# Block_Diagram.net
KiCad netlist of a schematic drawn in Altium Designer
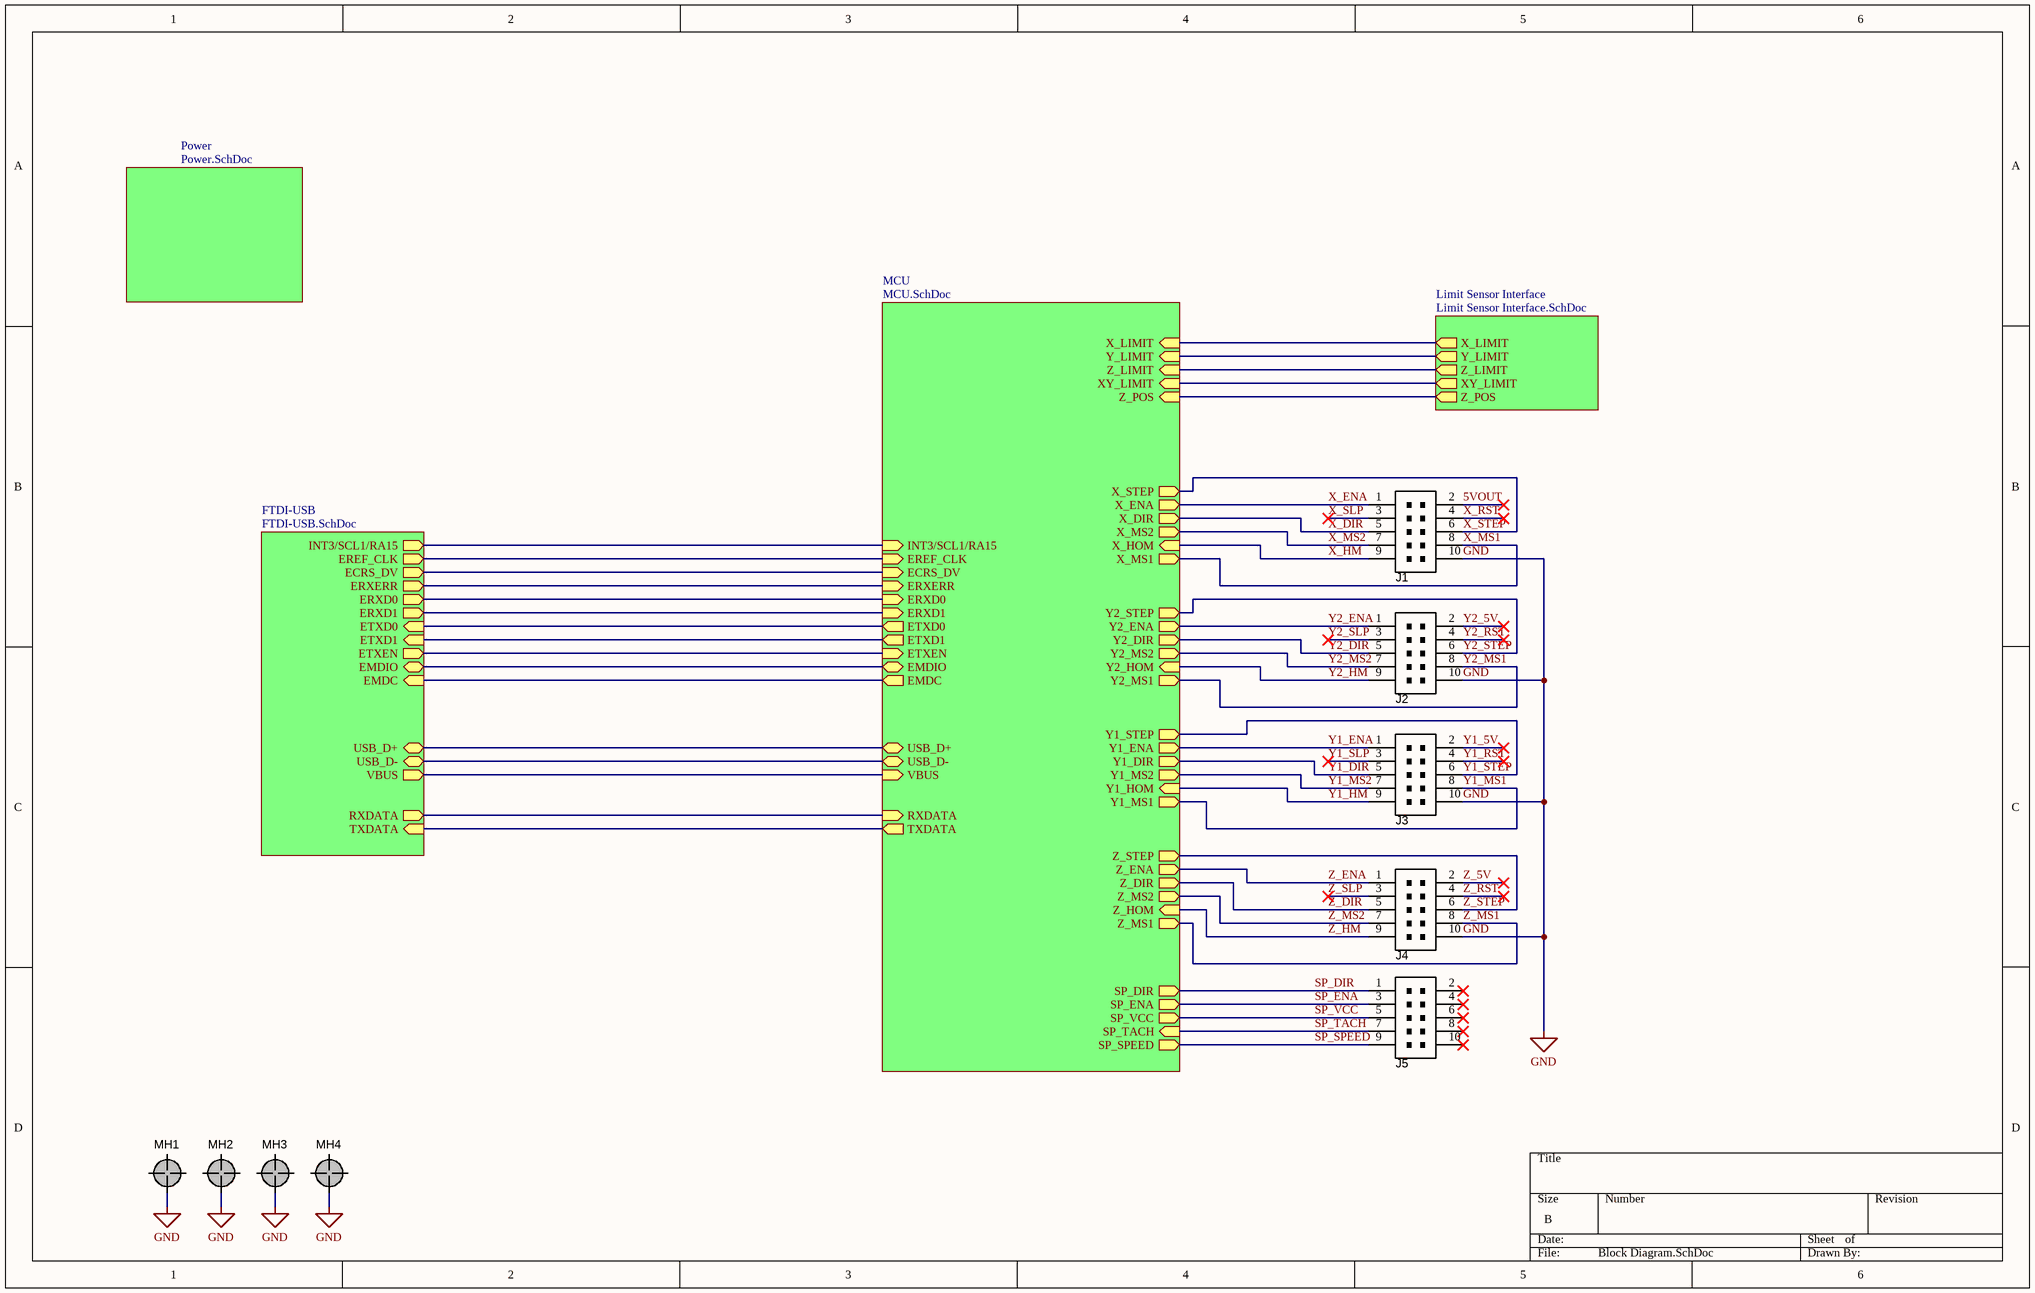
[diagram p0: Block Diagram.SchDoc]

(export (version "E")
  (design (tool "Eeschema 10.0.6"))
  (components
    (comp (ref "J1")
      (value "shrouded box header")
      (footprint "10P_PCB_HEADER_BRD_MNT")
      (description "Header THD 10 POS Double-row 2.54mm pitch")
      (libsource (lib "PBL - Connectors") (part "CONN_HEADER_2x5P_0.100in_Male"))
    )
    (comp (ref "J2")
      (value "shrouded box header")
      (footprint "10P_PCB_HEADER_BRD_MNT")
      (description "Header THD 10 POS Double-row 2.54mm pitch")
      (libsource (lib "PBL - Connectors") (part "CONN_HEADER_2x5P_0.100in_Male"))
    )
    (comp (ref "J3")
      (value "shrouded box header")
      (footprint "10P_PCB_HEADER_BRD_MNT")
      (description "Header THD 10 POS Double-row 2.54mm pitch")
      (libsource (lib "PBL - Connectors") (part "CONN_HEADER_2x5P_0.100in_Male"))
    )
    (comp (ref "J4")
      (value "shrouded box header")
      (footprint "10P_PCB_HEADER_BRD_MNT")
      (description "Header THD 10 POS Double-row 2.54mm pitch")
      (libsource (lib "PBL - Connectors") (part "CONN_HEADER_2x5P_0.100in_Male"))
    )
    (comp (ref "J5")
      (value "shrouded box header")
      (footprint "10P_PCB_HEADER_BRD_MNT")
      (description "Header THD 10 POS Double-row 2.54mm pitch")
      (libsource (lib "PBL - Connectors") (part "CONN_HEADER_2x5P_0.100in_Male"))
    )
    (comp (ref "MH1")
      (value "MH_Plated_125mil")
      (footprint "MH_PLATED_125 ID x 260mil OD")
      (libsource (lib "PBL - Pads and Jumpers") (part "MH_Plated_125mil"))
    )
    (comp (ref "MH2")
      (value "MH_Plated_125mil")
      (footprint "MH_PLATED_125 ID x 260mil OD")
      (libsource (lib "PBL - Pads and Jumpers") (part "MH_Plated_125mil"))
    )
    (comp (ref "MH3")
      (value "MH_Plated_125mil")
      (footprint "MH_PLATED_125 ID x 260mil OD")
      (libsource (lib "PBL - Pads and Jumpers") (part "MH_Plated_125mil"))
    )
    (comp (ref "MH4")
      (value "MH_Plated_125mil")
      (footprint "MH_PLATED_125 ID x 260mil OD")
      (libsource (lib "PBL - Pads and Jumpers") (part "MH_Plated_125mil"))
    )
  )
  (nets
    (net (code "1") (name "/5VOUT") (class "Default")
      (node (ref "J1") (pin "2") (pinfunction "2_2") (pintype "passive+no_connect"))
    )
    (net (code "14") (name "/SP_DIR") (class "Default")
      (node (ref "J5") (pin "1") (pinfunction "1_1") (pintype "passive"))
    )
    (net (code "15") (name "/SP_ENA") (class "Default")
      (node (ref "J5") (pin "3") (pinfunction "3_3") (pintype "passive"))
    )
    (net (code "16") (name "/SP_SPEED") (class "Default")
      (node (ref "J5") (pin "9") (pinfunction "9_9") (pintype "passive"))
    )
    (net (code "17") (name "/SP_TACH") (class "Default")
      (node (ref "J5") (pin "7") (pinfunction "7_7") (pintype "passive"))
    )
    (net (code "18") (name "/SP_VCC") (class "Default")
      (node (ref "J5") (pin "5") (pinfunction "5_5") (pintype "passive"))
    )
    (net (code "24") (name "/X_DIR") (class "Default")
      (node (ref "J1") (pin "5") (pinfunction "5_5") (pintype "passive"))
    )
    (net (code "25") (name "/X_ENA") (class "Default")
      (node (ref "J1") (pin "1") (pinfunction "1_1") (pintype "passive"))
    )
    (net (code "26") (name "/X_HM") (class "Default")
      (node (ref "J1") (pin "9") (pinfunction "9_9") (pintype "passive"))
    )
    (net (code "28") (name "/X_MS1") (class "Default")
      (node (ref "J1") (pin "8") (pinfunction "8_8") (pintype "passive"))
    )
    (net (code "29") (name "/X_MS2") (class "Default")
      (node (ref "J1") (pin "7") (pinfunction "7_7") (pintype "passive"))
    )
    (net (code "30") (name "/X_RST") (class "Default")
      (node (ref "J1") (pin "4") (pinfunction "4_4") (pintype "passive+no_connect"))
    )
    (net (code "31") (name "/X_SLP") (class "Default")
      (node (ref "J1") (pin "3") (pinfunction "3_3") (pintype "passive+no_connect"))
    )
    (net (code "32") (name "/X_STEP") (class "Default")
      (node (ref "J1") (pin "6") (pinfunction "6_6") (pintype "passive"))
    )
    (net (code "33") (name "/Y1_5V") (class "Default")
      (node (ref "J3") (pin "2") (pinfunction "2_2") (pintype "passive+no_connect"))
    )
    (net (code "34") (name "/Y1_DIR") (class "Default")
      (node (ref "J3") (pin "5") (pinfunction "5_5") (pintype "passive"))
    )
    (net (code "35") (name "/Y1_ENA") (class "Default")
      (node (ref "J3") (pin "1") (pinfunction "1_1") (pintype "passive"))
    )
    (net (code "36") (name "/Y1_HM") (class "Default")
      (node (ref "J3") (pin "9") (pinfunction "9_9") (pintype "passive"))
    )
    (net (code "37") (name "/Y1_MS1") (class "Default")
      (node (ref "J3") (pin "8") (pinfunction "8_8") (pintype "passive"))
    )
    (net (code "38") (name "/Y1_MS2") (class "Default")
      (node (ref "J3") (pin "7") (pinfunction "7_7") (pintype "passive"))
    )
    (net (code "39") (name "/Y1_RST") (class "Default")
      (node (ref "J3") (pin "4") (pinfunction "4_4") (pintype "passive+no_connect"))
    )
    (net (code "40") (name "/Y1_SLP") (class "Default")
      (node (ref "J3") (pin "3") (pinfunction "3_3") (pintype "passive+no_connect"))
    )
    (net (code "41") (name "/Y1_STEP") (class "Default")
      (node (ref "J3") (pin "6") (pinfunction "6_6") (pintype "passive"))
    )
    (net (code "42") (name "/Y2_5V") (class "Default")
      (node (ref "J2") (pin "2") (pinfunction "2_2") (pintype "passive+no_connect"))
    )
    (net (code "43") (name "/Y2_DIR") (class "Default")
      (node (ref "J2") (pin "5") (pinfunction "5_5") (pintype "passive"))
    )
    (net (code "44") (name "/Y2_ENA") (class "Default")
      (node (ref "J2") (pin "1") (pinfunction "1_1") (pintype "passive"))
    )
    (net (code "45") (name "/Y2_HM") (class "Default")
      (node (ref "J2") (pin "9") (pinfunction "9_9") (pintype "passive"))
    )
    (net (code "46") (name "/Y2_MS1") (class "Default")
      (node (ref "J2") (pin "8") (pinfunction "8_8") (pintype "passive"))
    )
    (net (code "47") (name "/Y2_MS2") (class "Default")
      (node (ref "J2") (pin "7") (pinfunction "7_7") (pintype "passive"))
    )
    (net (code "48") (name "/Y2_RST") (class "Default")
      (node (ref "J2") (pin "4") (pinfunction "4_4") (pintype "passive+no_connect"))
    )
    (net (code "49") (name "/Y2_SLP") (class "Default")
      (node (ref "J2") (pin "3") (pinfunction "3_3") (pintype "passive+no_connect"))
    )
    (net (code "50") (name "/Y2_STEP") (class "Default")
      (node (ref "J2") (pin "6") (pinfunction "6_6") (pintype "passive"))
    )
    (net (code "52") (name "/Z_5V") (class "Default")
      (node (ref "J4") (pin "2") (pinfunction "2_2") (pintype "passive+no_connect"))
    )
    (net (code "53") (name "/Z_DIR") (class "Default")
      (node (ref "J4") (pin "5") (pinfunction "5_5") (pintype "passive"))
    )
    (net (code "54") (name "/Z_ENA") (class "Default")
      (node (ref "J4") (pin "1") (pinfunction "1_1") (pintype "passive"))
    )
    (net (code "55") (name "/Z_HM") (class "Default")
      (node (ref "J4") (pin "9") (pinfunction "9_9") (pintype "passive"))
    )
    (net (code "57") (name "/Z_MS1") (class "Default")
      (node (ref "J4") (pin "8") (pinfunction "8_8") (pintype "passive"))
    )
    (net (code "58") (name "/Z_MS2") (class "Default")
      (node (ref "J4") (pin "7") (pinfunction "7_7") (pintype "passive"))
    )
    (net (code "60") (name "/Z_RST") (class "Default")
      (node (ref "J4") (pin "4") (pinfunction "4_4") (pintype "passive+no_connect"))
    )
    (net (code "61") (name "/Z_SLP") (class "Default")
      (node (ref "J4") (pin "3") (pinfunction "3_3") (pintype "passive+no_connect"))
    )
    (net (code "62") (name "/Z_STEP") (class "Default")
      (node (ref "J4") (pin "6") (pinfunction "6_6") (pintype "passive"))
    )
    (net (code "63") (name "GND") (class "Default")
      (node (ref "J1") (pin "10") (pinfunction "10_10") (pintype "passive"))
      (node (ref "J2") (pin "10") (pinfunction "10_10") (pintype "passive"))
      (node (ref "J3") (pin "10") (pinfunction "10_10") (pintype "passive"))
      (node (ref "J4") (pin "10") (pinfunction "10_10") (pintype "passive"))
      (node (ref "MH1") (pin "MH") (pinfunction "MH_MH") (pintype "passive"))
      (node (ref "MH2") (pin "MH") (pinfunction "MH_MH") (pintype "passive"))
      (node (ref "MH3") (pin "MH") (pinfunction "MH_MH") (pintype "passive"))
      (node (ref "MH4") (pin "MH") (pinfunction "MH_MH") (pintype "passive"))
    )
    (net (code "64") (name "unconnected-(J5-Pad2)") (class "Default")
      (node (ref "J5") (pin "2") (pinfunction "2_2") (pintype "passive+no_connect"))
    )
    (net (code "65") (name "unconnected-(J5-Pad4)") (class "Default")
      (node (ref "J5") (pin "4") (pinfunction "4_4") (pintype "passive+no_connect"))
    )
    (net (code "66") (name "unconnected-(J5-Pad6)") (class "Default")
      (node (ref "J5") (pin "6") (pinfunction "6_6") (pintype "passive+no_connect"))
    )
    (net (code "67") (name "unconnected-(J5-Pad8)") (class "Default")
      (node (ref "J5") (pin "8") (pinfunction "8_8") (pintype "passive+no_connect"))
    )
    (net (code "68") (name "unconnected-(J5-Pad10)") (class "Default")
      (node (ref "J5") (pin "10") (pinfunction "10_10") (pintype "passive+no_connect"))
    )
  )
)
